# rel-2b-alu.net
KiCad netlist of a schematic drawn in EAGLE
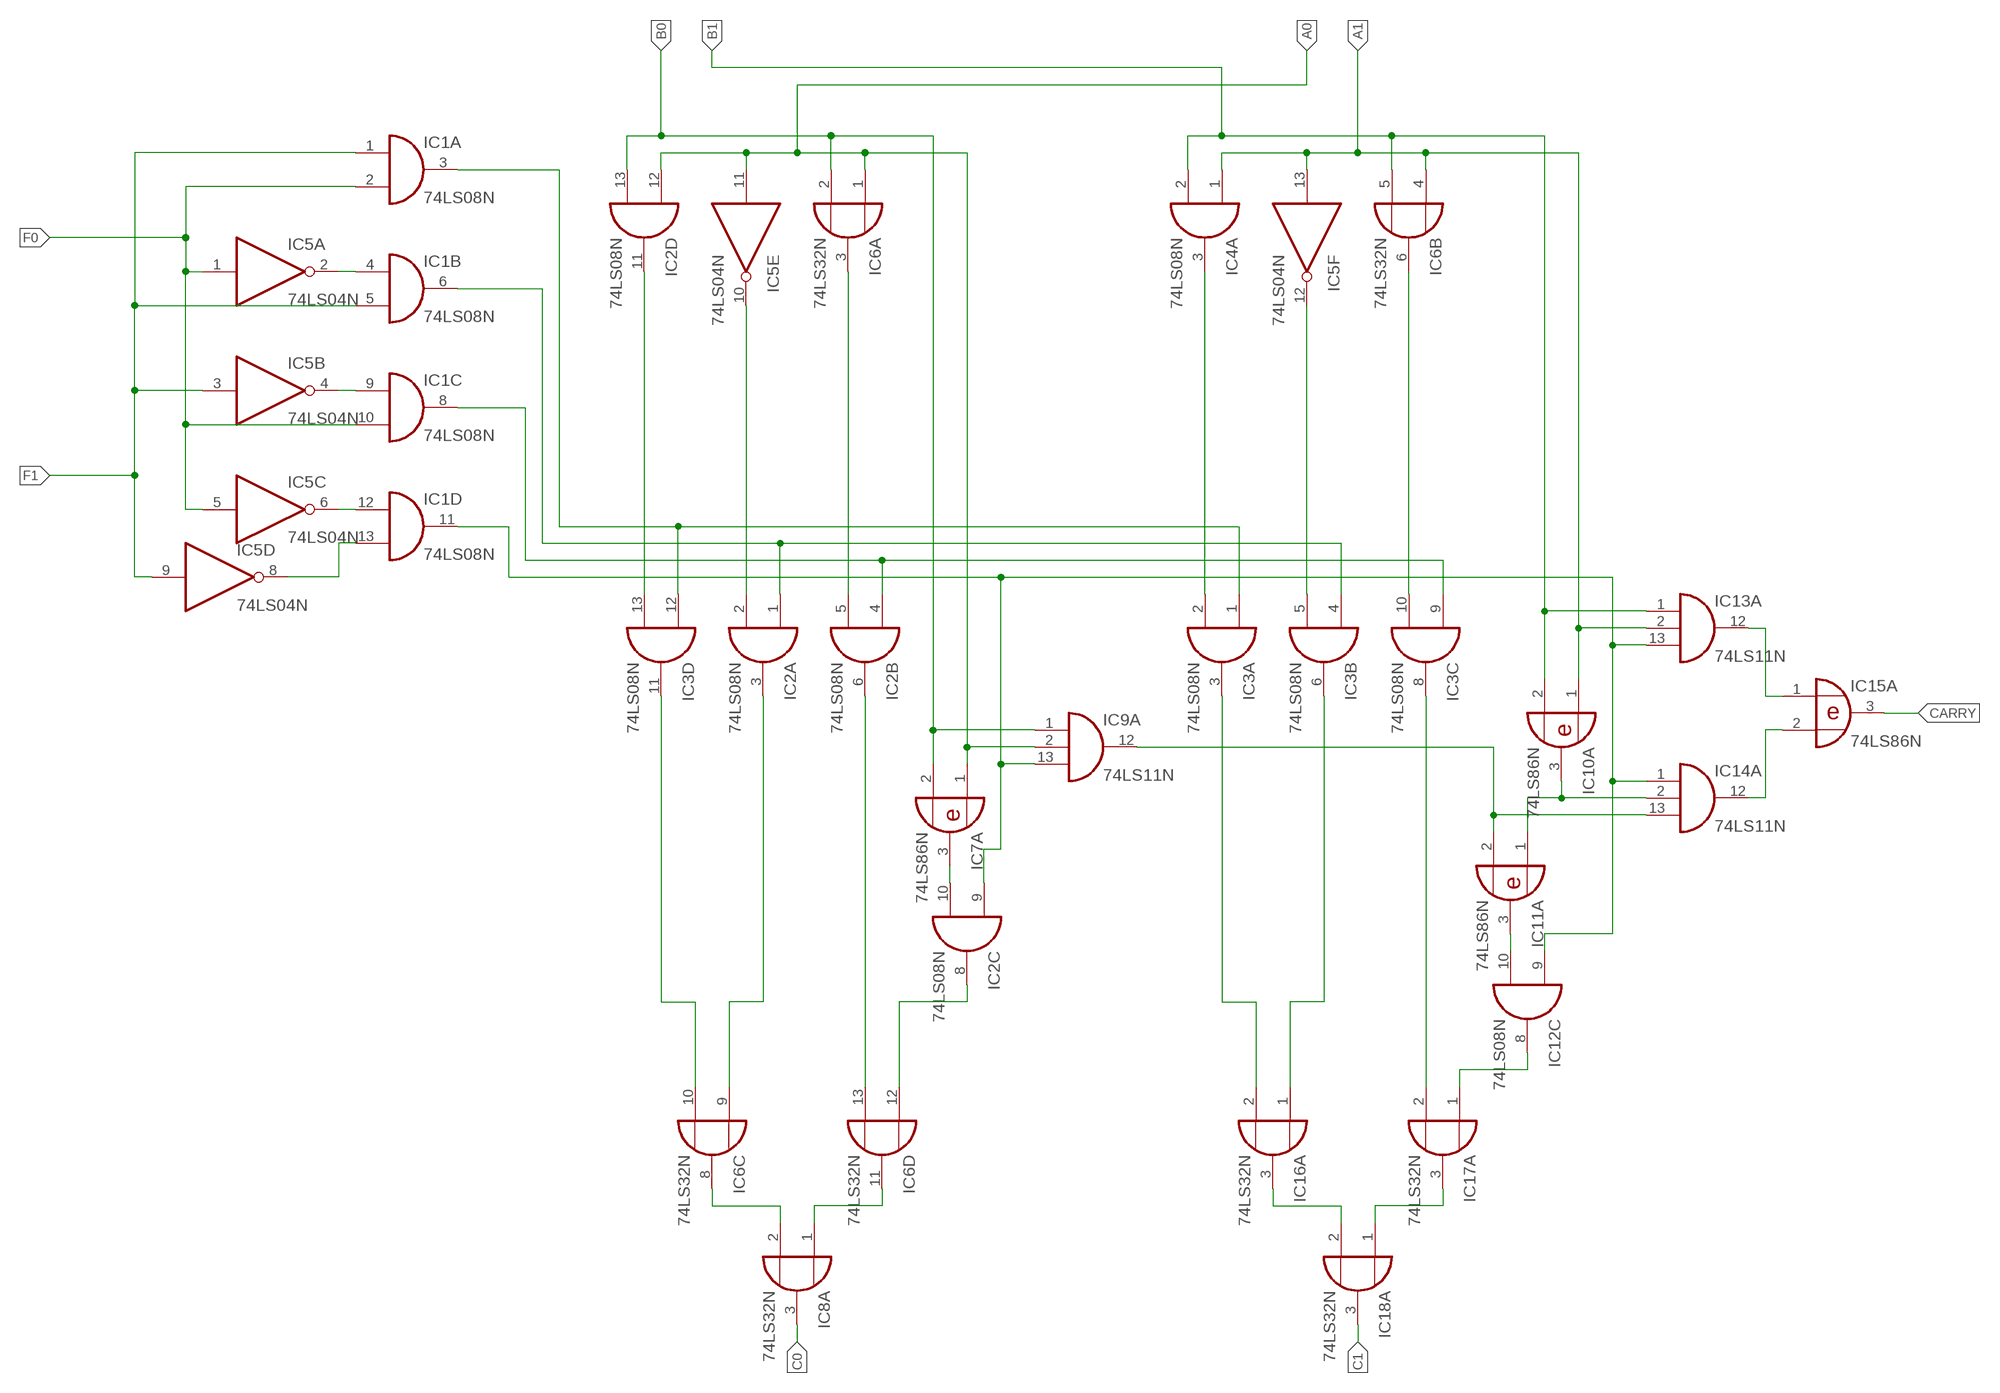
[diagram p0: schematic, sheet 1]

(export (version "E")
  (design (tool "Eeschema 10.0.6"))
  (components
    (comp (ref "IC1")
      (value "74LS08N")
      (footprint "eagle-import:DIL14")
      (libsource (lib "eagle-import") (part "7408NLS"))
    )
    (comp (ref "IC2")
      (value "74LS08N")
      (footprint "eagle-import:DIL14")
      (libsource (lib "eagle-import") (part "7408NLS"))
    )
    (comp (ref "IC3")
      (value "74LS08N")
      (footprint "eagle-import:DIL14")
      (libsource (lib "eagle-import") (part "7408NLS"))
    )
    (comp (ref "IC4")
      (value "74LS08N")
      (footprint "eagle-import:DIL14")
      (libsource (lib "eagle-import") (part "7408NLS"))
    )
    (comp (ref "IC5")
      (value "74LS04N")
      (footprint "eagle-import:DIL14")
      (libsource (lib "eagle-import") (part "7404NLS"))
    )
    (comp (ref "IC6")
      (value "74LS32N")
      (footprint "eagle-import:DIL14")
      (libsource (lib "eagle-import") (part "7432NLS"))
    )
    (comp (ref "IC7")
      (value "74LS86N")
      (footprint "eagle-import:DIL14")
      (libsource (lib "eagle-import") (part "7486NLS"))
    )
    (comp (ref "IC8")
      (value "74LS32N")
      (footprint "eagle-import:DIL14")
      (libsource (lib "eagle-import") (part "7432NLS"))
    )
    (comp (ref "IC9")
      (value "74LS11N")
      (footprint "eagle-import:DIL14")
      (libsource (lib "eagle-import") (part "7411NLS"))
    )
    (comp (ref "IC10")
      (value "74LS86N")
      (footprint "eagle-import:DIL14")
      (libsource (lib "eagle-import") (part "7486NLS"))
    )
    (comp (ref "IC11")
      (value "74LS86N")
      (footprint "eagle-import:DIL14")
      (libsource (lib "eagle-import") (part "7486NLS"))
    )
    (comp (ref "IC12")
      (value "74LS08N")
      (footprint "eagle-import:DIL14")
      (libsource (lib "eagle-import") (part "7408NLS"))
    )
    (comp (ref "IC13")
      (value "74LS11N")
      (footprint "eagle-import:DIL14")
      (libsource (lib "eagle-import") (part "7411NLS"))
    )
    (comp (ref "IC14")
      (value "74LS11N")
      (footprint "eagle-import:DIL14")
      (libsource (lib "eagle-import") (part "7411NLS"))
    )
    (comp (ref "IC15")
      (value "74LS86N")
      (footprint "eagle-import:DIL14")
      (libsource (lib "eagle-import") (part "7486NLS"))
    )
    (comp (ref "IC16")
      (value "74LS32N")
      (footprint "eagle-import:DIL14")
      (libsource (lib "eagle-import") (part "7432NLS"))
    )
    (comp (ref "IC17")
      (value "74LS32N")
      (footprint "eagle-import:DIL14")
      (libsource (lib "eagle-import") (part "7432NLS"))
    )
    (comp (ref "IC18")
      (value "74LS32N")
      (footprint "eagle-import:DIL14")
      (libsource (lib "eagle-import") (part "7432NLS"))
    )
  )
  (nets
    (net (code "1") (name "A0") (class "Default")
      (node (ref "IC2") (pin "12") (pinfunction "I0_12") (pintype "input"))
      (node (ref "IC5") (pin "11") (pinfunction "I_11") (pintype "input"))
      (node (ref "IC6") (pin "1") (pinfunction "I0_1") (pintype "input"))
      (node (ref "IC7") (pin "1") (pinfunction "I0_1") (pintype "input"))
      (node (ref "IC9") (pin "2") (pinfunction "I1_2") (pintype "input"))
    )
    (net (code "2") (name "A1") (class "Default")
      (node (ref "IC10") (pin "1") (pinfunction "I0_1") (pintype "input"))
      (node (ref "IC13") (pin "2") (pinfunction "I1_2") (pintype "input"))
      (node (ref "IC4") (pin "1") (pinfunction "I0_1") (pintype "input"))
      (node (ref "IC5") (pin "13") (pinfunction "I_13") (pintype "input"))
      (node (ref "IC6") (pin "4") (pinfunction "I0_4") (pintype "input"))
    )
    (net (code "3") (name "B0") (class "Default")
      (node (ref "IC2") (pin "13") (pinfunction "I1_13") (pintype "input"))
      (node (ref "IC6") (pin "2") (pinfunction "I1_2") (pintype "input"))
      (node (ref "IC7") (pin "2") (pinfunction "I1_2") (pintype "input"))
      (node (ref "IC9") (pin "1") (pinfunction "I0_1") (pintype "input"))
    )
    (net (code "4") (name "B1") (class "Default")
      (node (ref "IC10") (pin "2") (pinfunction "I1_2") (pintype "input"))
      (node (ref "IC13") (pin "1") (pinfunction "I0_1") (pintype "input"))
      (node (ref "IC4") (pin "2") (pinfunction "I1_2") (pintype "input"))
      (node (ref "IC6") (pin "5") (pinfunction "I1_5") (pintype "input"))
    )
    (net (code "5") (name "C0") (class "Default")
      (node (ref "IC8") (pin "3") (pinfunction "O_3") (pintype "output"))
    )
    (net (code "6") (name "C1") (class "Default")
      (node (ref "IC18") (pin "3") (pinfunction "O_3") (pintype "output"))
    )
    (net (code "7") (name "CARRY") (class "Default")
      (node (ref "IC15") (pin "3") (pinfunction "O_3") (pintype "output"))
    )
    (net (code "8") (name "F0") (class "Default")
      (node (ref "IC1") (pin "10") (pinfunction "I1_10") (pintype "input"))
      (node (ref "IC1") (pin "2") (pinfunction "I1_2") (pintype "input"))
      (node (ref "IC5") (pin "1") (pinfunction "I_1") (pintype "input"))
      (node (ref "IC5") (pin "5") (pinfunction "I_5") (pintype "input"))
    )
    (net (code "9") (name "F1") (class "Default")
      (node (ref "IC1") (pin "1") (pinfunction "I0_1") (pintype "input"))
      (node (ref "IC1") (pin "5") (pinfunction "I1_5") (pintype "input"))
      (node (ref "IC5") (pin "3") (pinfunction "I_3") (pintype "input"))
      (node (ref "IC5") (pin "9") (pinfunction "I_9") (pintype "input"))
    )
    (net (code "10") (name "Net-(IC1A-O)") (class "Default")
      (node (ref "IC1") (pin "3") (pinfunction "O_3") (pintype "output"))
      (node (ref "IC3") (pin "1") (pinfunction "I0_1") (pintype "input"))
      (node (ref "IC3") (pin "12") (pinfunction "I0_12") (pintype "input"))
    )
    (net (code "11") (name "Net-(IC1B-I0)") (class "Default")
      (node (ref "IC1") (pin "4") (pinfunction "I0_4") (pintype "input"))
      (node (ref "IC5") (pin "2") (pinfunction "O_2") (pintype "output"))
    )
    (net (code "12") (name "Net-(IC1B-O)") (class "Default")
      (node (ref "IC1") (pin "6") (pinfunction "O_6") (pintype "output"))
      (node (ref "IC2") (pin "1") (pinfunction "I0_1") (pintype "input"))
      (node (ref "IC3") (pin "4") (pinfunction "I0_4") (pintype "input"))
    )
    (net (code "13") (name "Net-(IC1C-I0)") (class "Default")
      (node (ref "IC1") (pin "9") (pinfunction "I0_9") (pintype "input"))
      (node (ref "IC5") (pin "4") (pinfunction "O_4") (pintype "output"))
    )
    (net (code "14") (name "Net-(IC1C-O)") (class "Default")
      (node (ref "IC1") (pin "8") (pinfunction "O_8") (pintype "output"))
      (node (ref "IC2") (pin "4") (pinfunction "I0_4") (pintype "input"))
      (node (ref "IC3") (pin "9") (pinfunction "I0_9") (pintype "input"))
    )
    (net (code "15") (name "Net-(IC1D-I0)") (class "Default")
      (node (ref "IC1") (pin "12") (pinfunction "I0_12") (pintype "input"))
      (node (ref "IC5") (pin "6") (pinfunction "O_6") (pintype "output"))
    )
    (net (code "16") (name "Net-(IC1D-I1)") (class "Default")
      (node (ref "IC1") (pin "13") (pinfunction "I1_13") (pintype "input"))
      (node (ref "IC5") (pin "8") (pinfunction "O_8") (pintype "output"))
    )
    (net (code "17") (name "Net-(IC2A-I1)") (class "Default")
      (node (ref "IC2") (pin "2") (pinfunction "I1_2") (pintype "input"))
      (node (ref "IC5") (pin "10") (pinfunction "O_10") (pintype "output"))
    )
    (net (code "18") (name "Net-(IC2A-O)") (class "Default")
      (node (ref "IC2") (pin "3") (pinfunction "O_3") (pintype "output"))
      (node (ref "IC6") (pin "9") (pinfunction "I0_9") (pintype "input"))
    )
    (net (code "19") (name "Net-(IC2B-I1)") (class "Default")
      (node (ref "IC2") (pin "5") (pinfunction "I1_5") (pintype "input"))
      (node (ref "IC6") (pin "3") (pinfunction "O_3") (pintype "output"))
    )
    (net (code "20") (name "Net-(IC2B-O)") (class "Default")
      (node (ref "IC2") (pin "6") (pinfunction "O_6") (pintype "output"))
      (node (ref "IC6") (pin "13") (pinfunction "I1_13") (pintype "input"))
    )
    (net (code "21") (name "Net-(IC2C-I1)") (class "Default")
      (node (ref "IC2") (pin "10") (pinfunction "I1_10") (pintype "input"))
      (node (ref "IC7") (pin "3") (pinfunction "O_3") (pintype "output"))
    )
    (net (code "22") (name "Net-(IC2C-O)") (class "Default")
      (node (ref "IC2") (pin "8") (pinfunction "O_8") (pintype "output"))
      (node (ref "IC6") (pin "12") (pinfunction "I0_12") (pintype "input"))
    )
    (net (code "23") (name "Net-(IC2D-O)") (class "Default")
      (node (ref "IC2") (pin "11") (pinfunction "O_11") (pintype "output"))
      (node (ref "IC3") (pin "13") (pinfunction "I1_13") (pintype "input"))
    )
    (net (code "24") (name "Net-(IC3A-I1)") (class "Default")
      (node (ref "IC3") (pin "2") (pinfunction "I1_2") (pintype "input"))
      (node (ref "IC4") (pin "3") (pinfunction "O_3") (pintype "output"))
    )
    (net (code "25") (name "Net-(IC3B-I1)") (class "Default")
      (node (ref "IC3") (pin "5") (pinfunction "I1_5") (pintype "input"))
      (node (ref "IC5") (pin "12") (pinfunction "O_12") (pintype "output"))
    )
    (net (code "26") (name "Net-(IC3C-I1)") (class "Default")
      (node (ref "IC3") (pin "10") (pinfunction "I1_10") (pintype "input"))
      (node (ref "IC6") (pin "6") (pinfunction "O_6") (pintype "output"))
    )
    (net (code "27") (name "Net-(IC3D-O)") (class "Default")
      (node (ref "IC3") (pin "11") (pinfunction "O_11") (pintype "output"))
      (node (ref "IC6") (pin "10") (pinfunction "I1_10") (pintype "input"))
    )
    (net (code "28") (name "Net-(IC6C-O)") (class "Default")
      (node (ref "IC6") (pin "8") (pinfunction "O_8") (pintype "output"))
      (node (ref "IC8") (pin "2") (pinfunction "I1_2") (pintype "input"))
    )
    (net (code "29") (name "Net-(IC6D-O)") (class "Default")
      (node (ref "IC6") (pin "11") (pinfunction "O_11") (pintype "output"))
      (node (ref "IC8") (pin "1") (pinfunction "I0_1") (pintype "input"))
    )
    (net (code "30") (name "Net-(IC10A-O)") (class "Default")
      (node (ref "IC10") (pin "3") (pinfunction "O_3") (pintype "output"))
      (node (ref "IC11") (pin "1") (pinfunction "I0_1") (pintype "input"))
      (node (ref "IC14") (pin "2") (pinfunction "I1_2") (pintype "input"))
    )
    (net (code "31") (name "Net-(IC11A-I1)") (class "Default")
      (node (ref "IC11") (pin "2") (pinfunction "I1_2") (pintype "input"))
      (node (ref "IC14") (pin "13") (pinfunction "I2_13") (pintype "input"))
      (node (ref "IC9") (pin "12") (pinfunction "O_12") (pintype "output"))
    )
    (net (code "32") (name "Net-(IC11A-O)") (class "Default")
      (node (ref "IC11") (pin "3") (pinfunction "O_3") (pintype "output"))
      (node (ref "IC12") (pin "10") (pinfunction "I1_10") (pintype "input"))
    )
    (net (code "33") (name "Net-(IC12C-I0)") (class "Default")
      (node (ref "IC1") (pin "11") (pinfunction "O_11") (pintype "output"))
      (node (ref "IC12") (pin "9") (pinfunction "I0_9") (pintype "input"))
      (node (ref "IC13") (pin "13") (pinfunction "I2_13") (pintype "input"))
      (node (ref "IC14") (pin "1") (pinfunction "I0_1") (pintype "input"))
      (node (ref "IC2") (pin "9") (pinfunction "I0_9") (pintype "input"))
      (node (ref "IC9") (pin "13") (pinfunction "I2_13") (pintype "input"))
    )
    (net (code "34") (name "Net-(IC12C-O)") (class "Default")
      (node (ref "IC12") (pin "8") (pinfunction "O_8") (pintype "output"))
      (node (ref "IC17") (pin "1") (pinfunction "I0_1") (pintype "input"))
    )
    (net (code "35") (name "Net-(IC13A-O)") (class "Default")
      (node (ref "IC13") (pin "12") (pinfunction "O_12") (pintype "output"))
      (node (ref "IC15") (pin "1") (pinfunction "I0_1") (pintype "input"))
    )
    (net (code "36") (name "Net-(IC14A-O)") (class "Default")
      (node (ref "IC14") (pin "12") (pinfunction "O_12") (pintype "output"))
      (node (ref "IC15") (pin "2") (pinfunction "I1_2") (pintype "input"))
    )
    (net (code "37") (name "Net-(IC16A-I0)") (class "Default")
      (node (ref "IC16") (pin "1") (pinfunction "I0_1") (pintype "input"))
      (node (ref "IC3") (pin "6") (pinfunction "O_6") (pintype "output"))
    )
    (net (code "38") (name "Net-(IC16A-I1)") (class "Default")
      (node (ref "IC16") (pin "2") (pinfunction "I1_2") (pintype "input"))
      (node (ref "IC3") (pin "3") (pinfunction "O_3") (pintype "output"))
    )
    (net (code "39") (name "Net-(IC16A-O)") (class "Default")
      (node (ref "IC16") (pin "3") (pinfunction "O_3") (pintype "output"))
      (node (ref "IC18") (pin "2") (pinfunction "I1_2") (pintype "input"))
    )
    (net (code "40") (name "Net-(IC17A-I1)") (class "Default")
      (node (ref "IC17") (pin "2") (pinfunction "I1_2") (pintype "input"))
      (node (ref "IC3") (pin "8") (pinfunction "O_8") (pintype "output"))
    )
    (net (code "41") (name "Net-(IC17A-O)") (class "Default")
      (node (ref "IC17") (pin "3") (pinfunction "O_3") (pintype "output"))
      (node (ref "IC18") (pin "1") (pinfunction "I0_1") (pintype "input"))
    )
  )
)
